# SM.net
KiCad netlist of a schematic drawn in Altium Designer
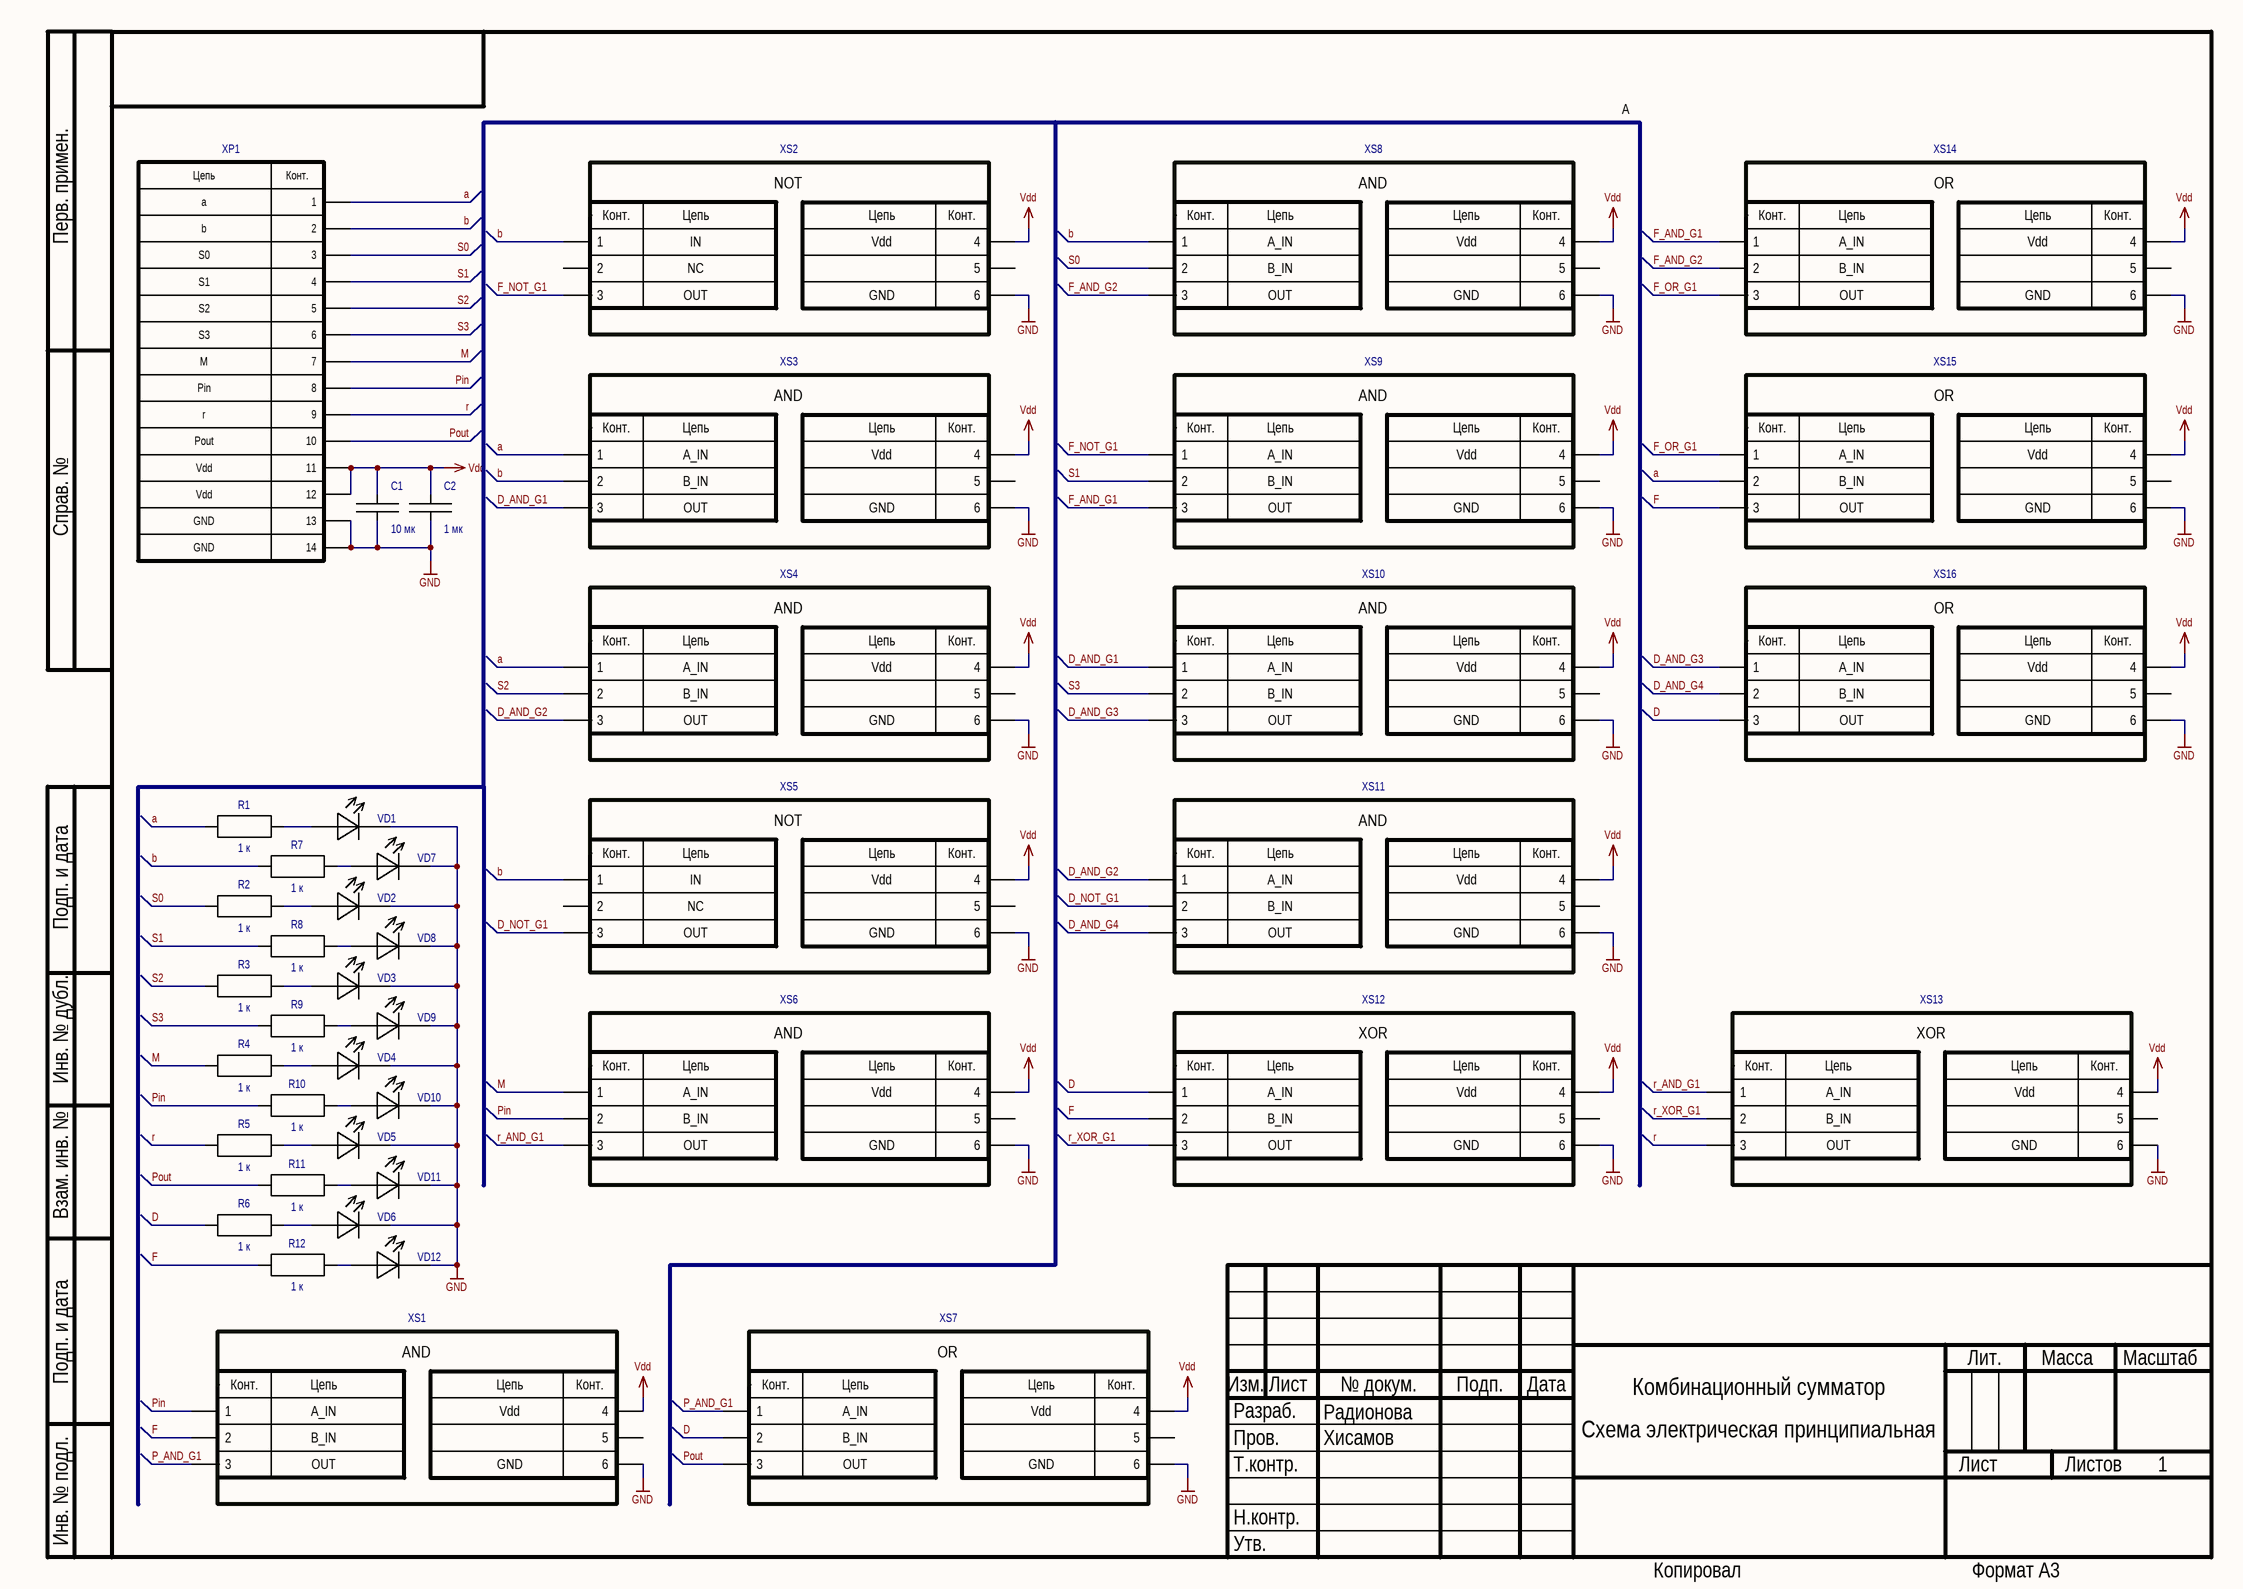
[diagram p0: SM.SchDoc]

(export (version "E")
  (design (tool "Eeschema 10.0.6"))
  (components
    (comp (ref "C1")
      (value "10 мк")
      (footprint "K10-79_1.6_0.8(0603)")
      (fields (field (name "Comment") "10 мкФ ±* * * 0805, *"))
      (libsource (lib "ALU") (part "C - Конденсатор"))
    )
    (comp (ref "C2")
      (value "1 мк")
      (footprint "K10-79_1.6_0.8(0603)")
      (fields (field (name "Comment") "1 мкФ ±* * * 0603, *"))
      (libsource (lib "ALU") (part "C - Конденсатор"))
    )
    (comp (ref "R1")
      (value "1 к")
      (footprint "P1-12-0.1(0603)")
      (fields (field (name "Comment") "1 кОм ±* 0603, *"))
      (libsource (lib "ALU") (part "R - Резистор"))
    )
    (comp (ref "R2")
      (value "1 к")
      (footprint "P1-12-0.1(0603)")
      (fields (field (name "Comment") "1 кОм ±* 0603, *"))
      (libsource (lib "ALU") (part "R - Резистор"))
    )
    (comp (ref "R3")
      (value "1 к")
      (footprint "P1-12-0.1(0603)")
      (fields (field (name "Comment") "1 кОм ±* 0603, *"))
      (libsource (lib "ALU") (part "R - Резистор"))
    )
    (comp (ref "R4")
      (value "1 к")
      (footprint "P1-12-0.1(0603)")
      (fields (field (name "Comment") "1 кОм ±* 0603, *"))
      (libsource (lib "ALU") (part "R - Резистор"))
    )
    (comp (ref "R5")
      (value "1 к")
      (footprint "P1-12-0.1(0603)")
      (fields (field (name "Comment") "1 кОм ±* 0603, *"))
      (libsource (lib "ALU") (part "R - Резистор"))
    )
    (comp (ref "R6")
      (value "1 к")
      (footprint "P1-12-0.1(0603)")
      (fields (field (name "Comment") "1 кОм ±* 0603, *"))
      (libsource (lib "ALU") (part "R - Резистор"))
    )
    (comp (ref "R7")
      (value "1 к")
      (footprint "P1-12-0.1(0603)")
      (fields (field (name "Comment") "1 кОм ±* 0603, *"))
      (libsource (lib "ALU") (part "R - Резистор"))
    )
    (comp (ref "R8")
      (value "1 к")
      (footprint "P1-12-0.1(0603)")
      (fields (field (name "Comment") "1 кОм ±* 0603, *"))
      (libsource (lib "ALU") (part "R - Резистор"))
    )
    (comp (ref "R9")
      (value "1 к")
      (footprint "P1-12-0.1(0603)")
      (fields (field (name "Comment") "1 кОм ±* 0603, *"))
      (libsource (lib "ALU") (part "R - Резистор"))
    )
    (comp (ref "R10")
      (value "1 к")
      (footprint "P1-12-0.1(0603)")
      (fields (field (name "Comment") "1 кОм ±* 0603, *"))
      (libsource (lib "ALU") (part "R - Резистор"))
    )
    (comp (ref "R11")
      (value "1 к")
      (footprint "P1-12-0.1(0603)")
      (fields (field (name "Comment") "1 кОм ±* 0603, *"))
      (libsource (lib "ALU") (part "R - Резистор"))
    )
    (comp (ref "R12")
      (value "1 к")
      (footprint "P1-12-0.1(0603)")
      (fields (field (name "Comment") "1 кОм ±* 0603, *"))
      (libsource (lib "ALU") (part "R - Резистор"))
    )
    (comp (ref "VD1")
      (value "VD - Светодиод")
      (footprint "LED 0603")
      (libsource (lib "ALU") (part "VD - Светодиод"))
    )
    (comp (ref "VD2")
      (value "VD - Светодиод")
      (footprint "LED 0603")
      (libsource (lib "ALU") (part "VD - Светодиод"))
    )
    (comp (ref "VD3")
      (value "VD - Светодиод")
      (footprint "LED 0603")
      (libsource (lib "ALU") (part "VD - Светодиод"))
    )
    (comp (ref "VD4")
      (value "VD - Светодиод")
      (footprint "LED 0603")
      (libsource (lib "ALU") (part "VD - Светодиод"))
    )
    (comp (ref "VD5")
      (value "VD - Светодиод")
      (footprint "LED 0603")
      (libsource (lib "ALU") (part "VD - Светодиод"))
    )
    (comp (ref "VD6")
      (value "VD - Светодиод")
      (footprint "LED 0603")
      (libsource (lib "ALU") (part "VD - Светодиод"))
    )
    (comp (ref "VD7")
      (value "VD - Светодиод")
      (footprint "LED 0603")
      (libsource (lib "ALU") (part "VD - Светодиод"))
    )
    (comp (ref "VD8")
      (value "VD - Светодиод")
      (footprint "LED 0603")
      (libsource (lib "ALU") (part "VD - Светодиод"))
    )
    (comp (ref "VD9")
      (value "VD - Светодиод")
      (footprint "LED 0603")
      (libsource (lib "ALU") (part "VD - Светодиод"))
    )
    (comp (ref "VD10")
      (value "VD - Светодиод")
      (footprint "LED 0603")
      (libsource (lib "ALU") (part "VD - Светодиод"))
    )
    (comp (ref "VD11")
      (value "VD - Светодиод")
      (footprint "LED 0603")
      (libsource (lib "ALU") (part "VD - Светодиод"))
    )
    (comp (ref "VD12")
      (value "VD - Светодиод")
      (footprint "LED 0603")
      (libsource (lib "ALU") (part "VD - Светодиод"))
    )
    (comp (ref "XP1")
      (value "XP - Вилка - х8")
      (footprint "PLD-16Norm")
      (libsource (lib "ALU") (part "XP - розетка- х14"))
    )
    (comp (ref "XS1")
      (value "Модуль AND")
      (footprint "модуль_AND")
      (description "модуль AND")
      (libsource (lib "ALU") (part "Модуль AND"))
    )
    (comp (ref "XS2")
      (value "Модуль NOT")
      (footprint "ALU:модуль_NOT")
      (description "модуль NOT")
      (libsource (lib "ALU") (part "Модуль NOT"))
    )
    (comp (ref "XS3")
      (value "Модуль AND")
      (footprint "модуль_AND")
      (description "модуль AND")
      (libsource (lib "ALU") (part "Модуль AND"))
    )
    (comp (ref "XS4")
      (value "Модуль AND")
      (footprint "модуль_AND")
      (description "модуль AND")
      (libsource (lib "ALU") (part "Модуль AND"))
    )
    (comp (ref "XS5")
      (value "Модуль NOT")
      (footprint "ALU:модуль_NOT")
      (description "модуль NOT")
      (libsource (lib "ALU") (part "Модуль NOT"))
    )
    (comp (ref "XS6")
      (value "Модуль AND")
      (footprint "модуль_AND")
      (description "модуль AND")
      (libsource (lib "ALU") (part "Модуль AND"))
    )
    (comp (ref "XS7")
      (value "Модуль OR")
      (footprint "ALU:модуль_OR")
      (description "модуль OR")
      (libsource (lib "ALU") (part "Модуль OR"))
    )
    (comp (ref "XS8")
      (value "Модуль AND")
      (footprint "модуль_AND")
      (description "модуль AND")
      (libsource (lib "ALU") (part "Модуль AND"))
    )
    (comp (ref "XS9")
      (value "Модуль AND")
      (footprint "модуль_AND")
      (description "модуль AND")
      (libsource (lib "ALU") (part "Модуль AND"))
    )
    (comp (ref "XS10")
      (value "Модуль AND")
      (footprint "модуль_AND")
      (description "модуль AND")
      (libsource (lib "ALU") (part "Модуль AND"))
    )
    (comp (ref "XS11")
      (value "Модуль AND")
      (footprint "модуль_AND")
      (description "модуль AND")
      (libsource (lib "ALU") (part "Модуль AND"))
    )
    (comp (ref "XS12")
      (value "Модуль XOR")
      (footprint "ALU:модуль_XOR")
      (description "модуль XOR")
      (libsource (lib "ALU") (part "Модуль XOR"))
    )
    (comp (ref "XS13")
      (value "Модуль XOR")
      (footprint "ALU:модуль_XOR")
      (description "модуль XOR")
      (libsource (lib "ALU") (part "Модуль XOR"))
    )
    (comp (ref "XS14")
      (value "Модуль OR")
      (footprint "модуль_OR")
      (description "модуль OR")
      (libsource (lib "ALU") (part "Модуль OR"))
    )
    (comp (ref "XS15")
      (value "Модуль OR")
      (footprint "модуль_OR")
      (description "модуль OR")
      (libsource (lib "ALU") (part "Модуль OR"))
    )
    (comp (ref "XS16")
      (value "Модуль OR")
      (footprint "модуль_OR")
      (description "модуль OR")
      (libsource (lib "ALU") (part "Модуль OR"))
    )
  )
  (nets
    (net (code "1") (name "/D") (class "Default")
      (node (ref "R6") (pin "1") (pinfunction "1_1") (pintype "passive"))
      (node (ref "XS12") (pin "1") (pinfunction "1_1") (pintype "passive"))
      (node (ref "XS16") (pin "3") (pinfunction "3_3") (pintype "passive"))
      (node (ref "XS7") (pin "2") (pinfunction "2_2") (pintype "passive"))
    )
    (net (code "2") (name "/D_AND_G1") (class "Default")
      (node (ref "XS10") (pin "1") (pinfunction "1_1") (pintype "passive"))
      (node (ref "XS3") (pin "3") (pinfunction "3_3") (pintype "passive"))
    )
    (net (code "3") (name "/D_AND_G2") (class "Default")
      (node (ref "XS11") (pin "1") (pinfunction "1_1") (pintype "passive"))
      (node (ref "XS4") (pin "3") (pinfunction "3_3") (pintype "passive"))
    )
    (net (code "4") (name "/D_AND_G3") (class "Default")
      (node (ref "XS10") (pin "3") (pinfunction "3_3") (pintype "passive"))
      (node (ref "XS16") (pin "1") (pinfunction "1_1") (pintype "passive"))
    )
    (net (code "5") (name "/D_AND_G4") (class "Default")
      (node (ref "XS11") (pin "3") (pinfunction "3_3") (pintype "passive"))
      (node (ref "XS16") (pin "2") (pinfunction "2_2") (pintype "passive"))
    )
    (net (code "6") (name "/D_NOT_G1") (class "Default")
      (node (ref "XS11") (pin "2") (pinfunction "2_2") (pintype "passive"))
      (node (ref "XS5") (pin "3") (pinfunction "3_3") (pintype "passive"))
    )
    (net (code "7") (name "/F") (class "Default")
      (node (ref "R12") (pin "1") (pinfunction "1_1") (pintype "passive"))
      (node (ref "XS1") (pin "2") (pinfunction "2_2") (pintype "passive"))
      (node (ref "XS12") (pin "2") (pinfunction "2_2") (pintype "passive"))
      (node (ref "XS15") (pin "3") (pinfunction "3_3") (pintype "passive"))
    )
    (net (code "8") (name "/F_AND_G1") (class "Default")
      (node (ref "XS14") (pin "1") (pinfunction "1_1") (pintype "passive"))
      (node (ref "XS9") (pin "3") (pinfunction "3_3") (pintype "passive"))
    )
    (net (code "9") (name "/F_AND_G2") (class "Default")
      (node (ref "XS14") (pin "2") (pinfunction "2_2") (pintype "passive"))
      (node (ref "XS8") (pin "3") (pinfunction "3_3") (pintype "passive"))
    )
    (net (code "10") (name "/F_NOT_G1") (class "Default")
      (node (ref "XS2") (pin "3") (pinfunction "3_3") (pintype "passive"))
      (node (ref "XS9") (pin "1") (pinfunction "1_1") (pintype "passive"))
    )
    (net (code "11") (name "/F_OR_G1") (class "Default")
      (node (ref "XS14") (pin "3") (pinfunction "3_3") (pintype "passive"))
      (node (ref "XS15") (pin "1") (pinfunction "1_1") (pintype "passive"))
    )
    (net (code "12") (name "/M") (class "Default")
      (node (ref "R4") (pin "1") (pinfunction "1_1") (pintype "passive"))
      (node (ref "XP1") (pin "7") (pinfunction "7_7") (pintype "passive"))
      (node (ref "XS6") (pin "1") (pinfunction "1_1") (pintype "passive"))
    )
    (net (code "13") (name "/P_AND_G1") (class "Default")
      (node (ref "XS1") (pin "3") (pinfunction "3_3") (pintype "passive"))
      (node (ref "XS7") (pin "1") (pinfunction "1_1") (pintype "passive"))
    )
    (net (code "14") (name "/Pin") (class "Default")
      (node (ref "R10") (pin "1") (pinfunction "1_1") (pintype "passive"))
      (node (ref "XP1") (pin "8") (pinfunction "8_8") (pintype "passive"))
      (node (ref "XS1") (pin "1") (pinfunction "1_1") (pintype "passive"))
      (node (ref "XS6") (pin "2") (pinfunction "2_2") (pintype "passive"))
    )
    (net (code "15") (name "/Pout") (class "Default")
      (node (ref "R11") (pin "1") (pinfunction "1_1") (pintype "passive"))
      (node (ref "XP1") (pin "10") (pinfunction "10_10") (pintype "passive"))
      (node (ref "XS7") (pin "3") (pinfunction "3_3") (pintype "passive"))
    )
    (net (code "16") (name "/S0") (class "Default")
      (node (ref "R2") (pin "1") (pinfunction "1_1") (pintype "passive"))
      (node (ref "XP1") (pin "3") (pinfunction "3_3") (pintype "passive"))
      (node (ref "XS8") (pin "2") (pinfunction "2_2") (pintype "passive"))
    )
    (net (code "17") (name "/S1") (class "Default")
      (node (ref "R8") (pin "1") (pinfunction "1_1") (pintype "passive"))
      (node (ref "XP1") (pin "4") (pinfunction "4_4") (pintype "passive"))
      (node (ref "XS9") (pin "2") (pinfunction "2_2") (pintype "passive"))
    )
    (net (code "18") (name "/S2") (class "Default")
      (node (ref "R3") (pin "1") (pinfunction "1_1") (pintype "passive"))
      (node (ref "XP1") (pin "5") (pinfunction "5_5") (pintype "passive"))
      (node (ref "XS4") (pin "2") (pinfunction "2_2") (pintype "passive"))
    )
    (net (code "19") (name "/S3") (class "Default")
      (node (ref "R9") (pin "1") (pinfunction "1_1") (pintype "passive"))
      (node (ref "XP1") (pin "6") (pinfunction "6_6") (pintype "passive"))
      (node (ref "XS10") (pin "2") (pinfunction "2_2") (pintype "passive"))
    )
    (net (code "20") (name "/a") (class "Default")
      (node (ref "R1") (pin "1") (pinfunction "1_1") (pintype "passive"))
      (node (ref "XP1") (pin "1") (pinfunction "1_1") (pintype "passive"))
      (node (ref "XS15") (pin "2") (pinfunction "2_2") (pintype "passive"))
      (node (ref "XS3") (pin "1") (pinfunction "1_1") (pintype "passive"))
      (node (ref "XS4") (pin "1") (pinfunction "1_1") (pintype "passive"))
    )
    (net (code "21") (name "/b") (class "Default")
      (node (ref "R7") (pin "1") (pinfunction "1_1") (pintype "passive"))
      (node (ref "XP1") (pin "2") (pinfunction "2_2") (pintype "passive"))
      (node (ref "XS2") (pin "1") (pinfunction "1_1") (pintype "passive"))
      (node (ref "XS3") (pin "2") (pinfunction "2_2") (pintype "passive"))
      (node (ref "XS5") (pin "1") (pinfunction "1_1") (pintype "passive"))
      (node (ref "XS8") (pin "1") (pinfunction "1_1") (pintype "passive"))
    )
    (net (code "22") (name "/r") (class "Default")
      (node (ref "R5") (pin "1") (pinfunction "1_1") (pintype "passive"))
      (node (ref "XP1") (pin "9") (pinfunction "9_9") (pintype "passive"))
      (node (ref "XS13") (pin "3") (pinfunction "3_3") (pintype "passive"))
    )
    (net (code "23") (name "/r_AND_G1") (class "Default")
      (node (ref "XS13") (pin "1") (pinfunction "1_1") (pintype "passive"))
      (node (ref "XS6") (pin "3") (pinfunction "3_3") (pintype "passive"))
    )
    (net (code "24") (name "/r_XOR_G1") (class "Default")
      (node (ref "XS12") (pin "3") (pinfunction "3_3") (pintype "passive"))
      (node (ref "XS13") (pin "2") (pinfunction "2_2") (pintype "passive"))
    )
    (net (code "25") (name "GND") (class "Default")
      (node (ref "C1") (pin "1") (pinfunction "1_1") (pintype "passive"))
      (node (ref "C2") (pin "1") (pinfunction "1_1") (pintype "passive"))
      (node (ref "VD1") (pin "2") (pinfunction "C_2") (pintype "passive"))
      (node (ref "VD10") (pin "2") (pinfunction "C_2") (pintype "passive"))
      (node (ref "VD11") (pin "2") (pinfunction "C_2") (pintype "passive"))
      (node (ref "VD12") (pin "2") (pinfunction "C_2") (pintype "passive"))
      (node (ref "VD2") (pin "2") (pinfunction "C_2") (pintype "passive"))
      (node (ref "VD3") (pin "2") (pinfunction "C_2") (pintype "passive"))
      (node (ref "VD4") (pin "2") (pinfunction "C_2") (pintype "passive"))
      (node (ref "VD5") (pin "2") (pinfunction "C_2") (pintype "passive"))
      (node (ref "VD6") (pin "2") (pinfunction "C_2") (pintype "passive"))
      (node (ref "VD7") (pin "2") (pinfunction "C_2") (pintype "passive"))
      (node (ref "VD8") (pin "2") (pinfunction "C_2") (pintype "passive"))
      (node (ref "VD9") (pin "2") (pinfunction "C_2") (pintype "passive"))
      (node (ref "XP1") (pin "13") (pinfunction "13_13") (pintype "passive"))
      (node (ref "XP1") (pin "14") (pinfunction "14_14") (pintype "passive"))
      (node (ref "XS1") (pin "6") (pinfunction "6_6") (pintype "passive"))
      (node (ref "XS10") (pin "6") (pinfunction "6_6") (pintype "passive"))
      (node (ref "XS11") (pin "6") (pinfunction "6_6") (pintype "passive"))
      (node (ref "XS12") (pin "6") (pinfunction "6_6") (pintype "passive"))
      (node (ref "XS13") (pin "6") (pinfunction "6_6") (pintype "passive"))
      (node (ref "XS14") (pin "6") (pinfunction "6_6") (pintype "passive"))
      (node (ref "XS15") (pin "6") (pinfunction "6_6") (pintype "passive"))
      (node (ref "XS16") (pin "6") (pinfunction "6_6") (pintype "passive"))
      (node (ref "XS2") (pin "6") (pinfunction "6_6") (pintype "passive"))
      (node (ref "XS3") (pin "6") (pinfunction "6_6") (pintype "passive"))
      (node (ref "XS4") (pin "6") (pinfunction "6_6") (pintype "passive"))
      (node (ref "XS5") (pin "6") (pinfunction "6_6") (pintype "passive"))
      (node (ref "XS6") (pin "6") (pinfunction "6_6") (pintype "passive"))
      (node (ref "XS7") (pin "6") (pinfunction "6_6") (pintype "passive"))
      (node (ref "XS8") (pin "6") (pinfunction "6_6") (pintype "passive"))
      (node (ref "XS9") (pin "6") (pinfunction "6_6") (pintype "passive"))
    )
    (net (code "26") (name "Net-(VD1-A)") (class "Default")
      (node (ref "R1") (pin "2") (pinfunction "2_2") (pintype "passive"))
      (node (ref "VD1") (pin "1") (pinfunction "A_1") (pintype "passive"))
    )
    (net (code "27") (name "Net-(VD2-A)") (class "Default")
      (node (ref "R2") (pin "2") (pinfunction "2_2") (pintype "passive"))
      (node (ref "VD2") (pin "1") (pinfunction "A_1") (pintype "passive"))
    )
    (net (code "28") (name "Net-(VD3-A)") (class "Default")
      (node (ref "R3") (pin "2") (pinfunction "2_2") (pintype "passive"))
      (node (ref "VD3") (pin "1") (pinfunction "A_1") (pintype "passive"))
    )
    (net (code "29") (name "Net-(VD4-A)") (class "Default")
      (node (ref "R4") (pin "2") (pinfunction "2_2") (pintype "passive"))
      (node (ref "VD4") (pin "1") (pinfunction "A_1") (pintype "passive"))
    )
    (net (code "30") (name "Net-(VD5-A)") (class "Default")
      (node (ref "R5") (pin "2") (pinfunction "2_2") (pintype "passive"))
      (node (ref "VD5") (pin "1") (pinfunction "A_1") (pintype "passive"))
    )
    (net (code "31") (name "Net-(VD6-A)") (class "Default")
      (node (ref "R6") (pin "2") (pinfunction "2_2") (pintype "passive"))
      (node (ref "VD6") (pin "1") (pinfunction "A_1") (pintype "passive"))
    )
    (net (code "32") (name "Net-(VD7-A)") (class "Default")
      (node (ref "R7") (pin "2") (pinfunction "2_2") (pintype "passive"))
      (node (ref "VD7") (pin "1") (pinfunction "A_1") (pintype "passive"))
    )
    (net (code "33") (name "Net-(VD8-A)") (class "Default")
      (node (ref "R8") (pin "2") (pinfunction "2_2") (pintype "passive"))
      (node (ref "VD8") (pin "1") (pinfunction "A_1") (pintype "passive"))
    )
    (net (code "34") (name "Net-(VD9-A)") (class "Default")
      (node (ref "R9") (pin "2") (pinfunction "2_2") (pintype "passive"))
      (node (ref "VD9") (pin "1") (pinfunction "A_1") (pintype "passive"))
    )
    (net (code "35") (name "Net-(VD10-A)") (class "Default")
      (node (ref "R10") (pin "2") (pinfunction "2_2") (pintype "passive"))
      (node (ref "VD10") (pin "1") (pinfunction "A_1") (pintype "passive"))
    )
    (net (code "36") (name "Net-(VD11-A)") (class "Default")
      (node (ref "R11") (pin "2") (pinfunction "2_2") (pintype "passive"))
      (node (ref "VD11") (pin "1") (pinfunction "A_1") (pintype "passive"))
    )
    (net (code "37") (name "Net-(VD12-A)") (class "Default")
      (node (ref "R12") (pin "2") (pinfunction "2_2") (pintype "passive"))
      (node (ref "VD12") (pin "1") (pinfunction "A_1") (pintype "passive"))
    )
    (net (code "38") (name "Vdd") (class "Default")
      (node (ref "C1") (pin "2") (pinfunction "2_2") (pintype "passive"))
      (node (ref "C2") (pin "2") (pinfunction "2_2") (pintype "passive"))
      (node (ref "XP1") (pin "11") (pinfunction "11_11") (pintype "passive"))
      (node (ref "XP1") (pin "12") (pinfunction "12_12") (pintype "passive"))
      (node (ref "XS1") (pin "4") (pinfunction "4_4") (pintype "passive"))
      (node (ref "XS10") (pin "4") (pinfunction "4_4") (pintype "passive"))
      (node (ref "XS11") (pin "4") (pinfunction "4_4") (pintype "passive"))
      (node (ref "XS12") (pin "4") (pinfunction "4_4") (pintype "passive"))
      (node (ref "XS13") (pin "4") (pinfunction "4_4") (pintype "passive"))
      (node (ref "XS14") (pin "4") (pinfunction "4_4") (pintype "passive"))
      (node (ref "XS15") (pin "4") (pinfunction "4_4") (pintype "passive"))
      (node (ref "XS16") (pin "4") (pinfunction "4_4") (pintype "passive"))
      (node (ref "XS2") (pin "4") (pinfunction "4_4") (pintype "passive"))
      (node (ref "XS3") (pin "4") (pinfunction "4_4") (pintype "passive"))
      (node (ref "XS4") (pin "4") (pinfunction "4_4") (pintype "passive"))
      (node (ref "XS5") (pin "4") (pinfunction "4_4") (pintype "passive"))
      (node (ref "XS6") (pin "4") (pinfunction "4_4") (pintype "passive"))
      (node (ref "XS7") (pin "4") (pinfunction "4_4") (pintype "passive"))
      (node (ref "XS8") (pin "4") (pinfunction "4_4") (pintype "passive"))
      (node (ref "XS9") (pin "4") (pinfunction "4_4") (pintype "passive"))
    )
    (net (code "39") (name "unconnected-(XS1-Pad5)") (class "Default")
      (node (ref "XS1") (pin "5") (pinfunction "5_5") (pintype "passive"))
    )
    (net (code "40") (name "unconnected-(XS2-Pad2)") (class "Default")
      (node (ref "XS2") (pin "2") (pinfunction "2_2") (pintype "passive"))
    )
    (net (code "41") (name "unconnected-(XS2-Pad5)") (class "Default")
      (node (ref "XS2") (pin "5") (pinfunction "5_5") (pintype "passive"))
    )
    (net (code "42") (name "unconnected-(XS3-Pad5)") (class "Default")
      (node (ref "XS3") (pin "5") (pinfunction "5_5") (pintype "passive"))
    )
    (net (code "43") (name "unconnected-(XS4-Pad5)") (class "Default")
      (node (ref "XS4") (pin "5") (pinfunction "5_5") (pintype "passive"))
    )
    (net (code "44") (name "unconnected-(XS5-Pad2)") (class "Default")
      (node (ref "XS5") (pin "2") (pinfunction "2_2") (pintype "passive"))
    )
    (net (code "45") (name "unconnected-(XS5-Pad5)") (class "Default")
      (node (ref "XS5") (pin "5") (pinfunction "5_5") (pintype "passive"))
    )
    (net (code "46") (name "unconnected-(XS6-Pad5)") (class "Default")
      (node (ref "XS6") (pin "5") (pinfunction "5_5") (pintype "passive"))
    )
    (net (code "47") (name "unconnected-(XS7-Pad5)") (class "Default")
      (node (ref "XS7") (pin "5") (pinfunction "5_5") (pintype "passive"))
    )
    (net (code "48") (name "unconnected-(XS8-Pad5)") (class "Default")
      (node (ref "XS8") (pin "5") (pinfunction "5_5") (pintype "passive"))
    )
    (net (code "49") (name "unconnected-(XS9-Pad5)") (class "Default")
      (node (ref "XS9") (pin "5") (pinfunction "5_5") (pintype "passive"))
    )
    (net (code "50") (name "unconnected-(XS10-Pad5)") (class "Default")
      (node (ref "XS10") (pin "5") (pinfunction "5_5") (pintype "passive"))
    )
    (net (code "51") (name "unconnected-(XS11-Pad5)") (class "Default")
      (node (ref "XS11") (pin "5") (pinfunction "5_5") (pintype "passive"))
    )
    (net (code "52") (name "unconnected-(XS12-Pad5)") (class "Default")
      (node (ref "XS12") (pin "5") (pinfunction "5_5") (pintype "passive"))
    )
    (net (code "53") (name "unconnected-(XS13-Pad5)") (class "Default")
      (node (ref "XS13") (pin "5") (pinfunction "5_5") (pintype "passive"))
    )
    (net (code "54") (name "unconnected-(XS14-Pad5)") (class "Default")
      (node (ref "XS14") (pin "5") (pinfunction "5_5") (pintype "passive"))
    )
    (net (code "55") (name "unconnected-(XS15-Pad5)") (class "Default")
      (node (ref "XS15") (pin "5") (pinfunction "5_5") (pintype "passive"))
    )
    (net (code "56") (name "unconnected-(XS16-Pad5)") (class "Default")
      (node (ref "XS16") (pin "5") (pinfunction "5_5") (pintype "passive"))
    )
  )
)
